# design.net
KiCad netlist of a schematic drawn in Altium Designer
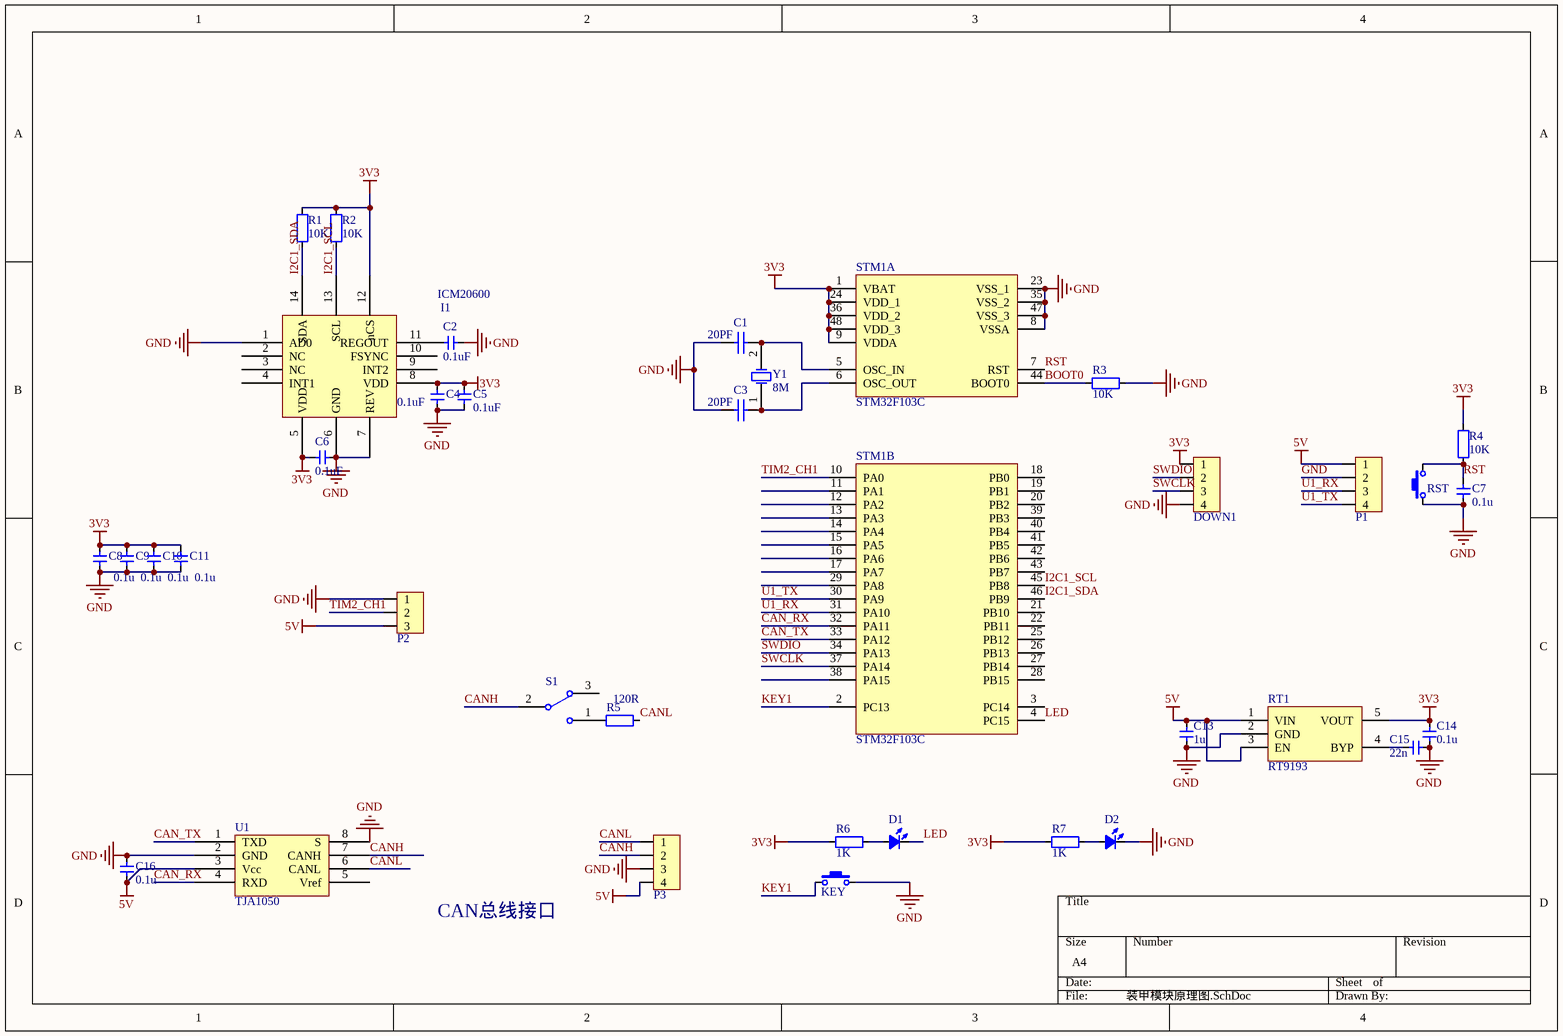
[diagram p0: 装甲模块原理图.SchDoc]

(export (version "E")
  (design (tool "Eeschema 10.0.6"))
  (components
    (comp (ref "C1")
      (value "20PF")
      (footprint "CAP_0603")
      (description "Capacitor")
      (fields (field (name "Comment") "Cap") (field (name "PUBLISHER") "Altium Limited"))
      (libsource (lib "K60-mainboard-v3.1") (part "Cap_1"))
    )
    (comp (ref "C2")
      (value "0.1uF")
      (footprint "PCB_PassiveCap:CAP_0603")
      (description "Capacitor")
      (fields (field (name "Comment") "Cap_0603"))
      (libsource (lib "SCH_Passive") (part "Cap_0603"))
    )
    (comp (ref "C3")
      (value "20PF")
      (footprint "CAP_0603")
      (description "Capacitor")
      (fields (field (name "Comment") "Cap") (field (name "PUBLISHER") "Altium Limited"))
      (libsource (lib "K60-mainboard-v3.1") (part "Cap_1"))
    )
    (comp (ref "C4")
      (value "0.1uF")
      (footprint "PCB_PassiveCap:CAP_0603")
      (description "Capacitor")
      (fields (field (name "Comment") "Cap_0603"))
      (libsource (lib "SCH_Passive") (part "Cap_0603"))
    )
    (comp (ref "C5")
      (value "0.1uF")
      (footprint "PCB_PassiveCap:CAP_0603")
      (description "Capacitor")
      (fields (field (name "Comment") "Cap_0603"))
      (libsource (lib "SCH_Passive") (part "Cap_0603"))
    )
    (comp (ref "C6")
      (value "0.1uF")
      (footprint "PCB_PassiveCap:CAP_0603")
      (description "Capacitor")
      (fields (field (name "Comment") "Cap_0603"))
      (libsource (lib "SCH_Passive") (part "Cap_0603"))
    )
    (comp (ref "C7")
      (value "0.1u")
      (footprint "PCB_PassiveCap:CAP_0603")
      (description "Capacitor")
      (fields (field (name "Comment") "Cap_0603"))
      (libsource (lib "SCH_Passive") (part "CAP_0603"))
    )
    (comp (ref "C8")
      (value "0.1u")
      (footprint "PCB_PassiveCap:CAP_0603")
      (description "Capacitor")
      (fields (field (name "Comment") "Cap_0603"))
      (libsource (lib "SCH_Passive") (part "CAP_0603"))
    )
    (comp (ref "C9")
      (value "0.1u")
      (footprint "PCB_PassiveCap:CAP_0603")
      (description "Capacitor")
      (fields (field (name "Comment") "Cap_0603"))
      (libsource (lib "SCH_Passive") (part "CAP_0603"))
    )
    (comp (ref "C10")
      (value "0.1u")
      (footprint "PCB_PassiveCap:CAP_0603")
      (description "Capacitor")
      (fields (field (name "Comment") "Cap_0603"))
      (libsource (lib "SCH_Passive") (part "CAP_0603"))
    )
    (comp (ref "C11")
      (value "0.1u")
      (footprint "PCB_PassiveCap:CAP_0603")
      (description "Capacitor")
      (fields (field (name "Comment") "Cap_0603"))
      (libsource (lib "SCH_Passive") (part "CAP_0603"))
    )
    (comp (ref "C13")
      (value "1u")
      (footprint "PCB_PassiveCap:CAP_0603")
      (description "Capacitor")
      (fields (field (name "Comment") "Cap_0603"))
      (libsource (lib "SCH_Passive") (part "Cap_0603"))
    )
    (comp (ref "C14")
      (value "0.1u")
      (footprint "PCB_PassiveCap:CAP_0603")
      (description "Capacitor")
      (fields (field (name "Comment") "Cap_0603"))
      (libsource (lib "SCH_Passive") (part "Cap_0603"))
    )
    (comp (ref "C15")
      (value "22n")
      (footprint "PCB_PassiveCap:CAP_0603")
      (description "Capacitor")
      (fields (field (name "Comment") "Cap_0603"))
      (libsource (lib "SCH_Passive") (part "Cap_0603"))
    )
    (comp (ref "C16")
      (value "0.1u")
      (footprint "PCB_PassiveCap:CAP_0603")
      (description "Capacitor")
      (fields (field (name "Comment") "Cap_0603"))
      (libsource (lib "SCH_Passive") (part "CAP_0603"))
    )
    (comp (ref "D1")
      (value "LED_0805")
      (footprint "PCB_ActiveLED:LED_0805_RED")
      (description "LED")
      (libsource (lib "SCH_Active") (part "LED_0805"))
    )
    (comp (ref "D2")
      (value "LED_0805")
      (footprint "PCB_ActiveLED:LED_0805_RED")
      (description "LED")
      (libsource (lib "SCH_Active") (part "LED_0805"))
    )
    (comp (ref "DOWN1")
      (value "HDR1x4_2.54")
      (footprint "PCB_ConnectorHDR:HDR1X4_2.54_SMD")
      (description "Header")
      (libsource (lib "SCH_ConnectorHDR") (part "HDR1x4_2.54"))
    )
    (comp (ref "I1")
      (value "ICM20600")
      (footprint "ICM20600")
      (libsource (lib "SCH_IntegratedCircuit") (part "ICM20600"))
    )
    (comp (ref "KEY")
      (value "ButtonTACT_3x4x2_180")
      (footprint "PCB_Switch:ButtonTACT_3x4x2_180H")
      (description "Button")
      (libsource (lib "SCH_Switch") (part "ButtonTACT_3x4x2_180"))
    )
    (comp (ref "P1")
      (value "HDR1x4_2.54")
      (footprint "PCB_ConnectorHDR:HDR1X4_2.54_SMD")
      (description "Header")
      (libsource (lib "SCH_ConnectorHDR") (part "HDR1x4_2.54"))
    )
    (comp (ref "P2")
      (value "HDR1x3_2.54")
      (footprint "PCB_ConnectorHDR:XH2.54_SMT_3PIN")
      (description "Header")
      (libsource (lib "SCH_ConnectorHDR") (part "HDR1x3_2.54"))
    )
    (comp (ref "P3")
      (value "HDR1x4_2.54")
      (footprint "PCB_ConnectorHDR:XH2.54_SMT_4PIN")
      (description "Header")
      (libsource (lib "SCH_ConnectorHDR") (part "HDR1x4_2.54"))
    )
    (comp (ref "R1")
      (value "10K")
      (footprint "PCB_PassiveRes:RES_0603")
      (description "Resistor")
      (fields (field (name "Comment") "Res_0603"))
      (libsource (lib "SCH_Passive") (part "Res_0603"))
    )
    (comp (ref "R2")
      (value "10K")
      (footprint "PCB_PassiveRes:RES_0603")
      (description "Resistor")
      (fields (field (name "Comment") "Res_0603"))
      (libsource (lib "SCH_Passive") (part "Res_0603"))
    )
    (comp (ref "R3")
      (value "10K")
      (footprint "RES_0603")
      (description "Resistor")
      (fields (field (name "Comment") "RES_0603"))
      (libsource (lib "SCH_Passive") (part "RES_0603"))
    )
    (comp (ref "R4")
      (value "10K")
      (footprint "RES_0603")
      (description "Resistor")
      (fields (field (name "Comment") "RES_0603"))
      (libsource (lib "") (part "RES_0603_1"))
    )
    (comp (ref "R5")
      (value "120R")
      (footprint "RES_0603")
      (description "Resistor")
      (fields (field (name "Comment") "RES_0603"))
      (libsource (lib "SCH_Passive") (part "RES_0603"))
    )
    (comp (ref "R6")
      (value "1K")
      (footprint "RES_0603")
      (description "Resistor")
      (fields (field (name "Comment") "RES_0603"))
      (libsource (lib "SCH_Passive") (part "RES_0603"))
    )
    (comp (ref "R7")
      (value "1K")
      (footprint "RES_0603")
      (description "Resistor")
      (fields (field (name "Comment") "RES_0603"))
      (libsource (lib "SCH_Passive") (part "RES_0603"))
    )
    (comp (ref "RST")
      (value "ButtonTACT_3x4x2_180")
      (footprint "PCB_Switch:ButtonTACT_3x4x2_180H")
      (description "Button")
      (libsource (lib "SCH_Switch") (part "ButtonTACT_3x4x2_180"))
    )
    (comp (ref "RT1")
      (value "RT9193")
      (footprint "PCB_IntegratedCircuit:SOT23-5")
      (description "Power")
      (libsource (lib "SCH_IntegratedCircuit") (part "RT9193"))
    )
    (comp (ref "S1")
      (value "SwitchSPDT_2.8x6.6_90")
      (footprint "PCB_Switch:SwitchSPDT_2.8X6.6_90")
      (description "Switch")
      (libsource (lib "SCH_Switch") (part "SwitchSPDT_2.8x6.6_90"))
    )
    (comp (ref "STM1")
      (value "STM32F103C")
      (footprint "PCB_IntegratedCircuit:LQFP_P0.5_48")
      (description "MCU")
      (libsource (lib "SCH_IntegratedCircuit") (part "STM32F103C"))
    )
    (comp (ref "U1")
      (value "TJA1050")
      (footprint "SOP_E150_8")
      (libsource (lib "SCH_IntegratedCircuit") (part "TJA1050"))
    )
    (comp (ref "Y1")
      (value "8M")
      (footprint "Osc-6032")
      (description "Crystal Oscillator")
      (fields (field (name "PUBLISHER") "Altium Limited"))
      (libsource (lib "Libraries_2014_0618") (part "C-Osc"))
    )
  )
  (nets
    (net (code "1") (name "/BOOT0") (class "Default")
      (node (ref "R3") (pin "1") (pinfunction "1_1") (pintype "passive"))
      (node (ref "STM1") (pin "44") (pinfunction "BOOT0_44") (pintype "passive"))
    )
    (net (code "2") (name "/CANH") (class "Default")
      (node (ref "P3") (pin "2") (pinfunction "2_2") (pintype "passive"))
      (node (ref "S1") (pin "2") (pinfunction "2_2") (pintype "passive"))
      (node (ref "U1") (pin "7") (pinfunction "CANH_7") (pintype "passive"))
    )
    (net (code "3") (name "/CANL") (class "Default")
      (node (ref "P3") (pin "1") (pinfunction "1_1") (pintype "passive"))
      (node (ref "R5") (pin "2") (pinfunction "2_2") (pintype "passive"))
      (node (ref "U1") (pin "6") (pinfunction "CANL_6") (pintype "passive"))
    )
    (net (code "4") (name "/CAN_RX") (class "Default")
      (node (ref "STM1") (pin "32") (pinfunction "PA11_32") (pintype "passive"))
      (node (ref "U1") (pin "4") (pinfunction "RXD_4") (pintype "passive"))
    )
    (net (code "5") (name "/CAN_TX") (class "Default")
      (node (ref "STM1") (pin "33") (pinfunction "PA12_33") (pintype "passive"))
      (node (ref "U1") (pin "1") (pinfunction "TXD_1") (pintype "passive"))
    )
    (net (code "6") (name "/I2C1_SCL") (class "Default")
      (node (ref "I1") (pin "13") (pinfunction "SCL_13") (pintype "passive"))
      (node (ref "R2") (pin "2") (pinfunction "2_2") (pintype "passive"))
      (node (ref "STM1") (pin "45") (pinfunction "PB8_45") (pintype "passive"))
    )
    (net (code "7") (name "/I2C1_SDA") (class "Default")
      (node (ref "I1") (pin "14") (pinfunction "SDA_14") (pintype "passive"))
      (node (ref "R1") (pin "2") (pinfunction "2_2") (pintype "passive"))
      (node (ref "STM1") (pin "46") (pinfunction "PB9_46") (pintype "passive"))
    )
    (net (code "8") (name "/KEY1") (class "Default")
      (node (ref "KEY") (pin "1") (pinfunction "1_1") (pintype "passive"))
      (node (ref "STM1") (pin "2") (pinfunction "PC13_2") (pintype "passive"))
    )
    (net (code "9") (name "/LED") (class "Default")
      (node (ref "D1") (pin "2") (pinfunction "K_2") (pintype "passive"))
      (node (ref "STM1") (pin "4") (pinfunction "PC15_4") (pintype "passive"))
    )
    (net (code "10") (name "/RST") (class "Default")
      (node (ref "C7") (pin "2") (pinfunction "2_2") (pintype "passive"))
      (node (ref "R4") (pin "1") (pinfunction "1_1") (pintype "passive"))
      (node (ref "RST") (pin "2") (pinfunction "2_2") (pintype "passive"))
      (node (ref "STM1") (pin "7") (pinfunction "RST_7") (pintype "passive"))
    )
    (net (code "11") (name "/SWCLK") (class "Default")
      (node (ref "DOWN1") (pin "3") (pinfunction "3_3") (pintype "passive"))
      (node (ref "STM1") (pin "37") (pinfunction "PA14_37") (pintype "passive"))
    )
    (net (code "12") (name "/SWDIO") (class "Default")
      (node (ref "DOWN1") (pin "2") (pinfunction "2_2") (pintype "passive"))
      (node (ref "STM1") (pin "34") (pinfunction "PA13_34") (pintype "passive"))
    )
    (net (code "13") (name "/TIM2_CH1") (class "Default")
      (node (ref "P2") (pin "2") (pinfunction "2_2") (pintype "passive"))
      (node (ref "STM1") (pin "10") (pinfunction "PA0_10") (pintype "passive"))
    )
    (net (code "14") (name "/U1_RX") (class "Default")
      (node (ref "P1") (pin "3") (pinfunction "3_3") (pintype "passive"))
      (node (ref "STM1") (pin "31") (pinfunction "PA10_31") (pintype "passive"))
    )
    (net (code "15") (name "/U1_TX") (class "Default")
      (node (ref "P1") (pin "4") (pinfunction "4_4") (pintype "passive"))
      (node (ref "STM1") (pin "30") (pinfunction "PA9_30") (pintype "passive"))
    )
    (net (code "16") (name "3V3") (class "Default")
      (node (ref "C10") (pin "2") (pinfunction "2_2") (pintype "passive"))
      (node (ref "C11") (pin "2") (pinfunction "2_2") (pintype "passive"))
      (node (ref "C14") (pin "2") (pinfunction "2_2") (pintype "passive"))
      (node (ref "C4") (pin "1") (pinfunction "1_1") (pintype "passive"))
      (node (ref "C5") (pin "1") (pinfunction "1_1") (pintype "passive"))
      (node (ref "C6") (pin "2") (pinfunction "2_2") (pintype "passive"))
      (node (ref "C8") (pin "2") (pinfunction "2_2") (pintype "passive"))
      (node (ref "C9") (pin "2") (pinfunction "2_2") (pintype "passive"))
      (node (ref "DOWN1") (pin "1") (pinfunction "1_1") (pintype "passive"))
      (node (ref "I1") (pin "12") (pinfunction "nCS_12") (pintype "passive"))
      (node (ref "I1") (pin "5") (pinfunction "VDD_5") (pintype "passive"))
      (node (ref "I1") (pin "8") (pinfunction "VDD_8") (pintype "passive"))
      (node (ref "R1") (pin "1") (pinfunction "1_1") (pintype "passive"))
      (node (ref "R2") (pin "1") (pinfunction "1_1") (pintype "passive"))
      (node (ref "R4") (pin "2") (pinfunction "2_2") (pintype "passive"))
      (node (ref "R6") (pin "1") (pinfunction "1_1") (pintype "passive"))
      (node (ref "R7") (pin "1") (pinfunction "1_1") (pintype "passive"))
      (node (ref "RT1") (pin "5") (pinfunction "VOUT_5") (pintype "passive"))
      (node (ref "STM1") (pin "1") (pinfunction "VBAT_1") (pintype "passive"))
      (node (ref "STM1") (pin "24") (pinfunction "VDD_1_24") (pintype "passive"))
      (node (ref "STM1") (pin "36") (pinfunction "VDD_2_36") (pintype "passive"))
      (node (ref "STM1") (pin "48") (pinfunction "VDD_3_48") (pintype "passive"))
      (node (ref "STM1") (pin "9") (pinfunction "VDDA_9") (pintype "passive"))
    )
    (net (code "17") (name "5V") (class "Default")
      (node (ref "C13") (pin "2") (pinfunction "2_2") (pintype "passive"))
      (node (ref "C16") (pin "1") (pinfunction "1_1") (pintype "passive"))
      (node (ref "P1") (pin "1") (pinfunction "1_1") (pintype "passive"))
      (node (ref "P2") (pin "3") (pinfunction "3_3") (pintype "passive"))
      (node (ref "P3") (pin "4") (pinfunction "4_4") (pintype "passive"))
      (node (ref "RT1") (pin "1") (pinfunction "VIN_1") (pintype "passive"))
      (node (ref "RT1") (pin "3") (pinfunction "EN_3") (pintype "power_in"))
      (node (ref "U1") (pin "3") (pinfunction "Vcc_3") (pintype "passive"))
    )
    (net (code "18") (name "GND") (class "Default")
      (node (ref "C1") (pin "1") (pinfunction "1_1") (pintype "passive"))
      (node (ref "C10") (pin "1") (pinfunction "1_1") (pintype "passive"))
      (node (ref "C11") (pin "1") (pinfunction "1_1") (pintype "passive"))
      (node (ref "C13") (pin "1") (pinfunction "1_1") (pintype "passive"))
      (node (ref "C14") (pin "1") (pinfunction "1_1") (pintype "passive"))
      (node (ref "C15") (pin "1") (pinfunction "1_1") (pintype "passive"))
      (node (ref "C16") (pin "2") (pinfunction "2_2") (pintype "passive"))
      (node (ref "C2") (pin "2") (pinfunction "2_2") (pintype "passive"))
      (node (ref "C3") (pin "1") (pinfunction "1_1") (pintype "passive"))
      (node (ref "C4") (pin "2") (pinfunction "2_2") (pintype "passive"))
      (node (ref "C5") (pin "2") (pinfunction "2_2") (pintype "passive"))
      (node (ref "C6") (pin "1") (pinfunction "1_1") (pintype "passive"))
      (node (ref "C7") (pin "1") (pinfunction "1_1") (pintype "passive"))
      (node (ref "C8") (pin "1") (pinfunction "1_1") (pintype "passive"))
      (node (ref "C9") (pin "1") (pinfunction "1_1") (pintype "passive"))
      (node (ref "D2") (pin "2") (pinfunction "K_2") (pintype "passive"))
      (node (ref "DOWN1") (pin "4") (pinfunction "4_4") (pintype "passive"))
      (node (ref "I1") (pin "1") (pinfunction "AD0_1") (pintype "passive"))
      (node (ref "I1") (pin "6") (pinfunction "GND_6") (pintype "passive"))
      (node (ref "I1") (pin "7") (pinfunction "REV_7") (pintype "passive"))
      (node (ref "KEY") (pin "2") (pinfunction "2_2") (pintype "passive"))
      (node (ref "P1") (pin "2") (pinfunction "2_2") (pintype "passive"))
      (node (ref "P2") (pin "1") (pinfunction "1_1") (pintype "passive"))
      (node (ref "P3") (pin "3") (pinfunction "3_3") (pintype "passive"))
      (node (ref "R3") (pin "2") (pinfunction "2_2") (pintype "passive"))
      (node (ref "RST") (pin "1") (pinfunction "1_1") (pintype "passive"))
      (node (ref "RT1") (pin "2") (pinfunction "GND_2") (pintype "passive"))
      (node (ref "STM1") (pin "23") (pinfunction "VSS_1_23") (pintype "passive"))
      (node (ref "STM1") (pin "35") (pinfunction "VSS_2_35") (pintype "passive"))
      (node (ref "STM1") (pin "47") (pinfunction "VSS_3_47") (pintype "passive"))
      (node (ref "STM1") (pin "8") (pinfunction "VSSA_8") (pintype "passive"))
      (node (ref "U1") (pin "2") (pinfunction "GND_2") (pintype "passive"))
      (node (ref "U1") (pin "8") (pinfunction "S_8") (pintype "passive"))
    )
    (net (code "19") (name "Net-(D1-A)") (class "Default")
      (node (ref "D1") (pin "1") (pinfunction "A_1") (pintype "passive"))
      (node (ref "R6") (pin "2") (pinfunction "2_2") (pintype "passive"))
    )
    (net (code "20") (name "Net-(D2-A)") (class "Default")
      (node (ref "D2") (pin "1") (pinfunction "A_1") (pintype "passive"))
      (node (ref "R7") (pin "2") (pinfunction "2_2") (pintype "passive"))
    )
    (net (code "21") (name "Net-(I1-REGOUT)") (class "Default")
      (node (ref "C2") (pin "1") (pinfunction "1_1") (pintype "passive"))
      (node (ref "I1") (pin "11") (pinfunction "REGOUT_11") (pintype "passive"))
    )
    (net (code "22") (name "Net-(R5-Pad1)") (class "Default")
      (node (ref "R5") (pin "1") (pinfunction "1_1") (pintype "passive"))
      (node (ref "S1") (pin "1") (pinfunction "1_1") (pintype "passive"))
    )
    (net (code "23") (name "Net-(RT1-BYP)") (class "Default")
      (node (ref "C15") (pin "2") (pinfunction "2_2") (pintype "passive"))
      (node (ref "RT1") (pin "4") (pinfunction "BYP_4") (pintype "passive"))
    )
    (net (code "24") (name "Net-(STM1A-OSC_IN)") (class "Default")
      (node (ref "C1") (pin "2") (pinfunction "2_2") (pintype "passive"))
      (node (ref "STM1") (pin "5") (pinfunction "OSC_IN_5") (pintype "passive"))
      (node (ref "Y1") (pin "2") (pinfunction "OSC2_2") (pintype "passive"))
    )
    (net (code "25") (name "Net-(STM1A-OSC_OUT)") (class "Default")
      (node (ref "C3") (pin "2") (pinfunction "2_2") (pintype "passive"))
      (node (ref "STM1") (pin "6") (pinfunction "OSC_OUT_6") (pintype "passive"))
      (node (ref "Y1") (pin "1") (pinfunction "OSC1_1") (pintype "passive"))
    )
    (net (code "26") (name "unconnected-(I1-FSYNC-Pad10)") (class "Default")
      (node (ref "I1") (pin "10") (pinfunction "FSYNC_10") (pintype "passive"))
    )
    (net (code "27") (name "unconnected-(I1-INT1-Pad4)") (class "Default")
      (node (ref "I1") (pin "4") (pinfunction "INT1_4") (pintype "passive"))
    )
    (net (code "28") (name "unconnected-(I1-INT2-Pad9)") (class "Default")
      (node (ref "I1") (pin "9") (pinfunction "INT2_9") (pintype "passive"))
    )
    (net (code "29") (name "unconnected-(I1-NC-Pad2)") (class "Default")
      (node (ref "I1") (pin "2") (pinfunction "NC_2") (pintype "passive"))
    )
    (net (code "30") (name "unconnected-(I1-NC-Pad3)") (class "Default")
      (node (ref "I1") (pin "3") (pinfunction "NC_3") (pintype "passive"))
    )
    (net (code "31") (name "unconnected-(S1-Pad3)") (class "Default")
      (node (ref "S1") (pin "3") (pinfunction "3_3") (pintype "passive"))
    )
    (net (code "32") (name "unconnected-(STM1B-PA1-Pad11)") (class "Default")
      (node (ref "STM1") (pin "11") (pinfunction "PA1_11") (pintype "passive"))
    )
    (net (code "33") (name "unconnected-(STM1B-PA2-Pad12)") (class "Default")
      (node (ref "STM1") (pin "12") (pinfunction "PA2_12") (pintype "passive"))
    )
    (net (code "34") (name "unconnected-(STM1B-PA3-Pad13)") (class "Default")
      (node (ref "STM1") (pin "13") (pinfunction "PA3_13") (pintype "passive"))
    )
    (net (code "35") (name "unconnected-(STM1B-PA4-Pad14)") (class "Default")
      (node (ref "STM1") (pin "14") (pinfunction "PA4_14") (pintype "passive"))
    )
    (net (code "36") (name "unconnected-(STM1B-PA5-Pad15)") (class "Default")
      (node (ref "STM1") (pin "15") (pinfunction "PA5_15") (pintype "passive"))
    )
    (net (code "37") (name "unconnected-(STM1B-PA6-Pad16)") (class "Default")
      (node (ref "STM1") (pin "16") (pinfunction "PA6_16") (pintype "passive"))
    )
    (net (code "38") (name "unconnected-(STM1B-PA7-Pad17)") (class "Default")
      (node (ref "STM1") (pin "17") (pinfunction "PA7_17") (pintype "passive"))
    )
    (net (code "39") (name "unconnected-(STM1B-PA8-Pad29)") (class "Default")
      (node (ref "STM1") (pin "29") (pinfunction "PA8_29") (pintype "passive"))
    )
    (net (code "40") (name "unconnected-(STM1B-PA15-Pad38)") (class "Default")
      (node (ref "STM1") (pin "38") (pinfunction "PA15_38") (pintype "passive"))
    )
    (net (code "41") (name "unconnected-(STM1B-PB0-Pad18)") (class "Default")
      (node (ref "STM1") (pin "18") (pinfunction "PB0_18") (pintype "passive"))
    )
    (net (code "42") (name "unconnected-(STM1B-PB1-Pad19)") (class "Default")
      (node (ref "STM1") (pin "19") (pinfunction "PB1_19") (pintype "passive"))
    )
    (net (code "43") (name "unconnected-(STM1B-PB2-Pad20)") (class "Default")
      (node (ref "STM1") (pin "20") (pinfunction "PB2_20") (pintype "passive"))
    )
    (net (code "44") (name "unconnected-(STM1B-PB3-Pad39)") (class "Default")
      (node (ref "STM1") (pin "39") (pinfunction "PB3_39") (pintype "passive"))
    )
    (net (code "45") (name "unconnected-(STM1B-PB4-Pad40)") (class "Default")
      (node (ref "STM1") (pin "40") (pinfunction "PB4_40") (pintype "passive"))
    )
    (net (code "46") (name "unconnected-(STM1B-PB5-Pad41)") (class "Default")
      (node (ref "STM1") (pin "41") (pinfunction "PB5_41") (pintype "passive"))
    )
    (net (code "47") (name "unconnected-(STM1B-PB6-Pad42)") (class "Default")
      (node (ref "STM1") (pin "42") (pinfunction "PB6_42") (pintype "passive"))
    )
    (net (code "48") (name "unconnected-(STM1B-PB7-Pad43)") (class "Default")
      (node (ref "STM1") (pin "43") (pinfunction "PB7_43") (pintype "passive"))
    )
    (net (code "49") (name "unconnected-(STM1B-PB10-Pad21)") (class "Default")
      (node (ref "STM1") (pin "21") (pinfunction "PB10_21") (pintype "passive"))
    )
    (net (code "50") (name "unconnected-(STM1B-PB11-Pad22)") (class "Default")
      (node (ref "STM1") (pin "22") (pinfunction "PB11_22") (pintype "passive"))
    )
    (net (code "51") (name "unconnected-(STM1B-PB12-Pad25)") (class "Default")
      (node (ref "STM1") (pin "25") (pinfunction "PB12_25") (pintype "passive"))
    )
    (net (code "52") (name "unconnected-(STM1B-PB13-Pad26)") (class "Default")
      (node (ref "STM1") (pin "26") (pinfunction "PB13_26") (pintype "passive"))
    )
    (net (code "53") (name "unconnected-(STM1B-PB14-Pad27)") (class "Default")
      (node (ref "STM1") (pin "27") (pinfunction "PB14_27") (pintype "passive"))
    )
    (net (code "54") (name "unconnected-(STM1B-PB15-Pad28)") (class "Default")
      (node (ref "STM1") (pin "28") (pinfunction "PB15_28") (pintype "passive"))
    )
    (net (code "55") (name "unconnected-(STM1B-PC14-Pad3)") (class "Default")
      (node (ref "STM1") (pin "3") (pinfunction "PC14_3") (pintype "passive"))
    )
    (net (code "56") (name "unconnected-(U1-Vref-Pad5)") (class "Default")
      (node (ref "U1") (pin "5") (pinfunction "Vref_5") (pintype "passive"))
    )
  )
)
